# Ethernet.net
KiCad netlist of a schematic drawn in Altium Designer
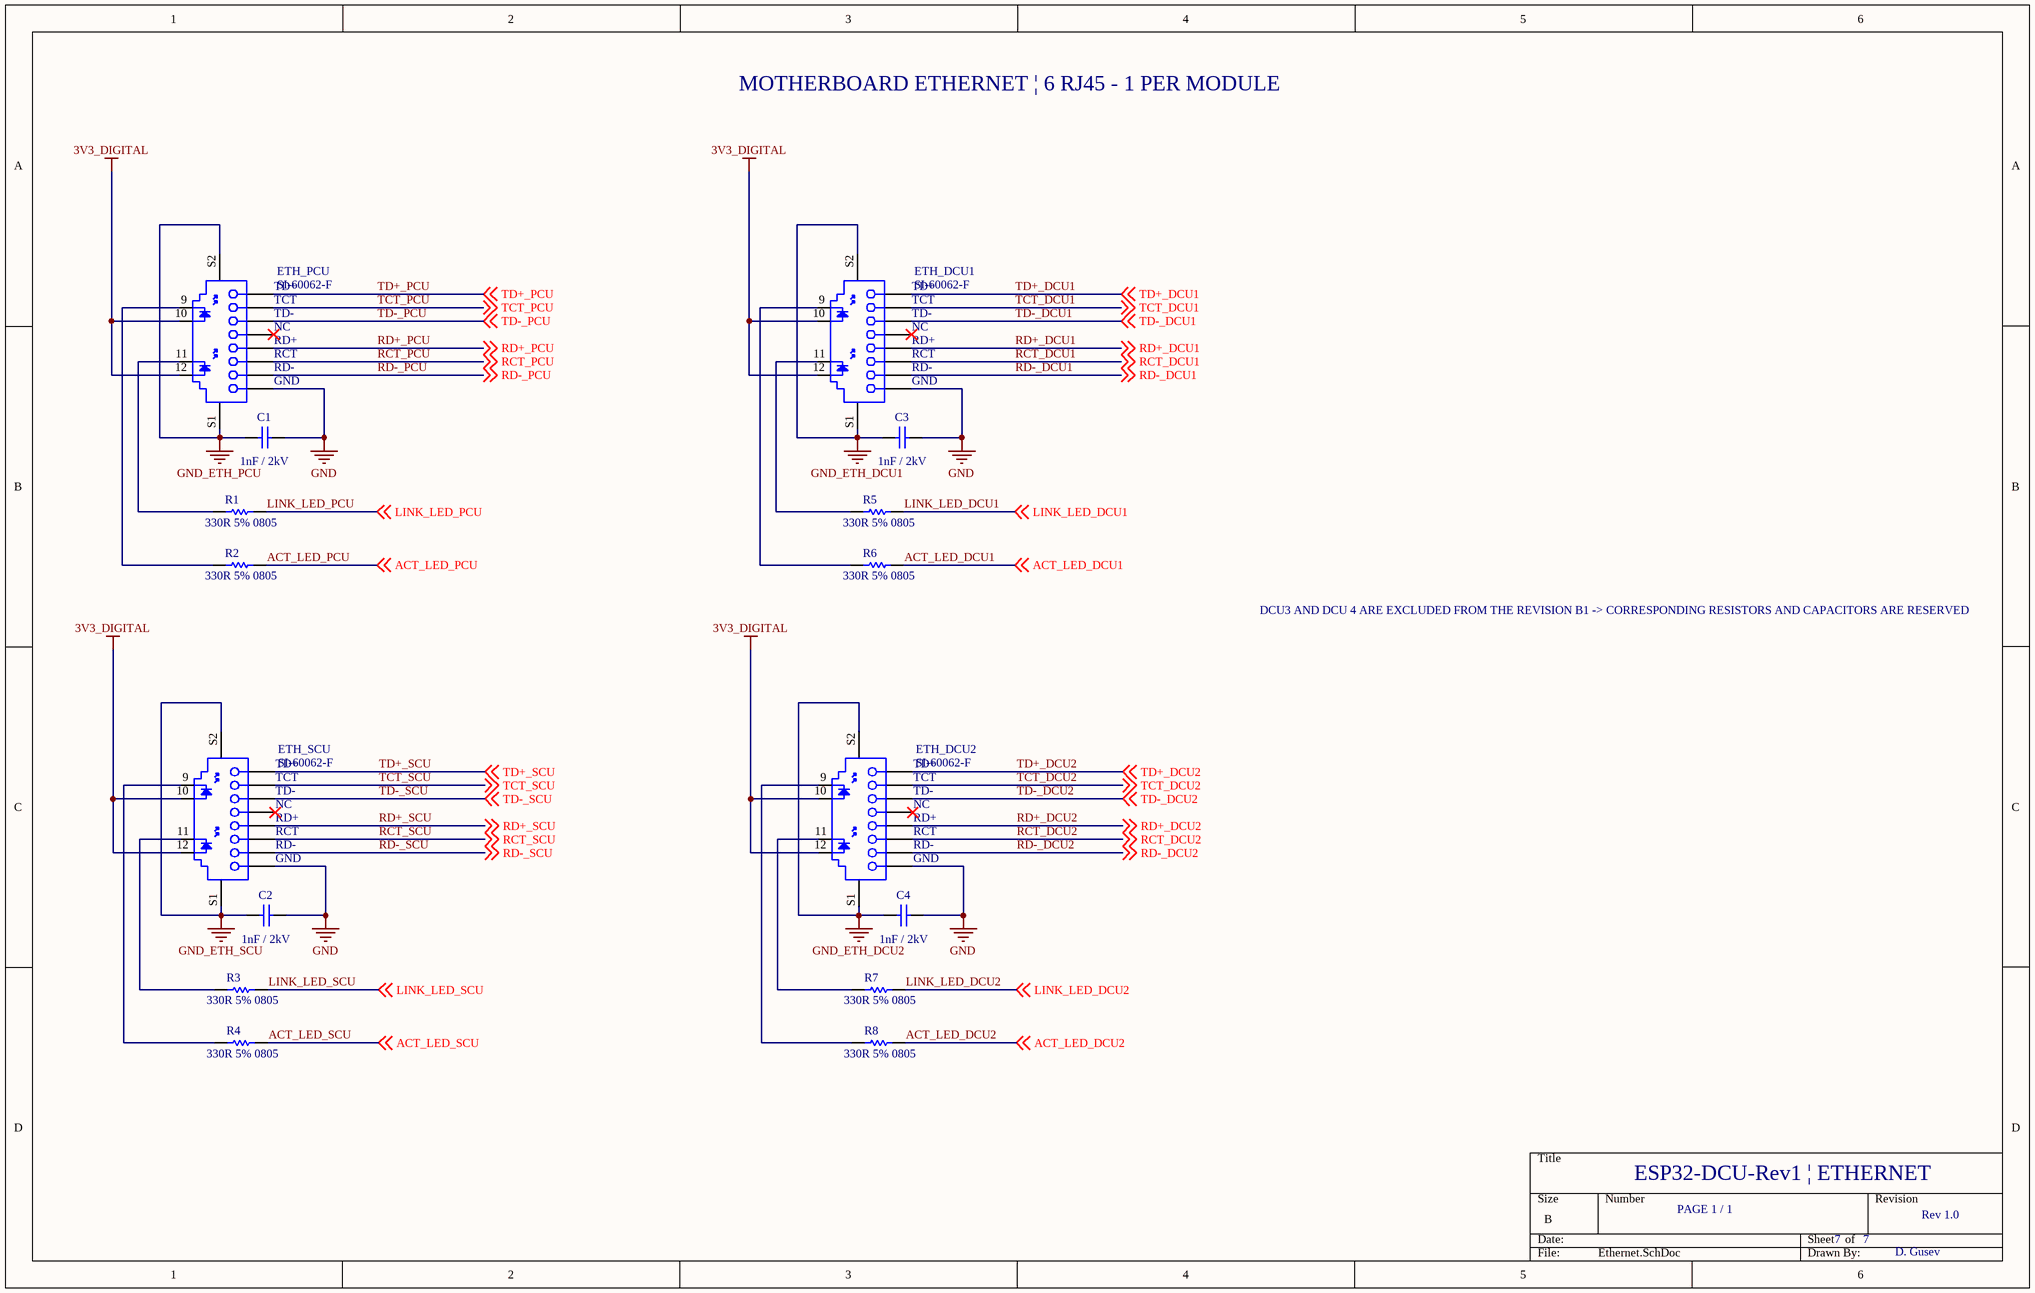
[diagram p0: Ethernet.SchDoc]

(export (version "E")
  (design (tool "Eeschema 10.0.6"))
  (components
    (comp (ref "C1")
      (value "1nF / 2kV")
      (footprint "CAPC4532X155X60LL30T35")
      (description "Chip Capacitor, 1000 pF, +/- 10%, 2000 V, -55 to 125 degC, 1812 (4532 Metric), RoHS, Tape and Reel")
      (fields (field (name "MANUFACTURER") "Kemet") (field (name "TOLERANCE") "±10%"))
      (libsource (lib "Altium Content Vault") (part "CAP-NP-2"))
    )
    (comp (ref "C2")
      (value "1nF / 2kV")
      (footprint "CAPC4532X155X60LL30T35")
      (description "Chip Capacitor, 1000 pF, +/- 10%, 2000 V, -55 to 125 degC, 1812 (4532 Metric), RoHS, Tape and Reel")
      (fields (field (name "MANUFACTURER") "Kemet") (field (name "TOLERANCE") "±10%"))
      (libsource (lib "Altium Content Vault") (part "CAP-NP-2"))
    )
    (comp (ref "C3")
      (value "1nF / 2kV")
      (footprint "CAPC4532X155X60LL30T35")
      (description "Chip Capacitor, 1000 pF, +/- 10%, 2000 V, -55 to 125 degC, 1812 (4532 Metric), RoHS, Tape and Reel")
      (fields (field (name "MANUFACTURER") "Kemet") (field (name "TOLERANCE") "±10%"))
      (libsource (lib "Altium Content Vault") (part "CAP-NP-2"))
    )
    (comp (ref "C4")
      (value "1nF / 2kV")
      (footprint "CAPC4532X155X60LL30T35")
      (description "Chip Capacitor, 1000 pF, +/- 10%, 2000 V, -55 to 125 degC, 1812 (4532 Metric), RoHS, Tape and Reel")
      (fields (field (name "MANUFACTURER") "Kemet") (field (name "TOLERANCE") "±10%"))
      (libsource (lib "Altium Content Vault") (part "CAP-NP-2"))
    )
    (comp (ref "ETH_DCU1")
      (value "SI-60062-F")
      (footprint "BELF-SI-60062-F_V")
      (description "1 Port RJ45 Magjack Connector with Yellow and Green LED, 10/100 Base-T, 12-Pin THD, RoHS, Tray")
      (fields (field (name "MANUFACTURER") "Bel Fuse"))
      (libsource (lib "Altium Content Vault") (part "RJ45-12-2SHLD"))
    )
    (comp (ref "ETH_DCU2")
      (value "SI-60062-F")
      (footprint "BELF-SI-60062-F_V")
      (description "1 Port RJ45 Magjack Connector with Yellow and Green LED, 10/100 Base-T, 12-Pin THD, RoHS, Tray")
      (fields (field (name "MANUFACTURER") "Bel Fuse"))
      (libsource (lib "Altium Content Vault") (part "RJ45-12-2SHLD"))
    )
    (comp (ref "ETH_PCU")
      (value "SI-60062-F")
      (footprint "BELF-SI-60062-F_V")
      (description "1 Port RJ45 Magjack Connector with Yellow and Green LED, 10/100 Base-T, 12-Pin THD, RoHS, Tray")
      (fields (field (name "MANUFACTURER") "Bel Fuse"))
      (libsource (lib "Altium Content Vault") (part "RJ45-12-2SHLD"))
    )
    (comp (ref "ETH_SCU")
      (value "SI-60062-F")
      (footprint "BELF-SI-60062-F_V")
      (description "1 Port RJ45 Magjack Connector with Yellow and Green LED, 10/100 Base-T, 12-Pin THD, RoHS, Tray")
      (fields (field (name "MANUFACTURER") "Bel Fuse"))
      (libsource (lib "Altium Content Vault") (part "RJ45-12-2SHLD"))
    )
    (comp (ref "R1")
      (value "330R 5% 0805")
      (footprint "RESC2013X60X35LL10T20")
      (description "Chip Resistor, 330 Ohm, +/- 1%, 125 mW, -55 to 155 degC, 0805 (2012 Metric), RoHS, Tape and Reel")
      (fields (field (name "MANUFACTURER") "Yageo") (field (name "TOLERANCE") "1%"))
      (libsource (lib "Altium Content Vault") (part "RES-2"))
    )
    (comp (ref "R2")
      (value "330R 5% 0805")
      (footprint "RESC2013X60X35LL10T20")
      (description "Chip Resistor, 330 Ohm, +/- 1%, 125 mW, -55 to 155 degC, 0805 (2012 Metric), RoHS, Tape and Reel")
      (fields (field (name "MANUFACTURER") "Yageo") (field (name "TOLERANCE") "1%"))
      (libsource (lib "Altium Content Vault") (part "RES-2"))
    )
    (comp (ref "R3")
      (value "330R 5% 0805")
      (footprint "RESC2013X60X35LL10T20")
      (description "Chip Resistor, 330 Ohm, +/- 1%, 125 mW, -55 to 155 degC, 0805 (2012 Metric), RoHS, Tape and Reel")
      (fields (field (name "MANUFACTURER") "Yageo") (field (name "TOLERANCE") "1%"))
      (libsource (lib "Altium Content Vault") (part "RES-2"))
    )
    (comp (ref "R4")
      (value "330R 5% 0805")
      (footprint "RESC2013X60X35LL10T20")
      (description "Chip Resistor, 330 Ohm, +/- 1%, 125 mW, -55 to 155 degC, 0805 (2012 Metric), RoHS, Tape and Reel")
      (fields (field (name "MANUFACTURER") "Yageo") (field (name "TOLERANCE") "1%"))
      (libsource (lib "Altium Content Vault") (part "RES-2"))
    )
    (comp (ref "R5")
      (value "330R 5% 0805")
      (footprint "RESC2013X60X35LL10T20")
      (description "Chip Resistor, 330 Ohm, +/- 1%, 125 mW, -55 to 155 degC, 0805 (2012 Metric), RoHS, Tape and Reel")
      (fields (field (name "MANUFACTURER") "Yageo") (field (name "TOLERANCE") "1%"))
      (libsource (lib "Altium Content Vault") (part "RES-2"))
    )
    (comp (ref "R6")
      (value "330R 5% 0805")
      (footprint "RESC2013X60X35LL10T20")
      (description "Chip Resistor, 330 Ohm, +/- 1%, 125 mW, -55 to 155 degC, 0805 (2012 Metric), RoHS, Tape and Reel")
      (fields (field (name "MANUFACTURER") "Yageo") (field (name "TOLERANCE") "1%"))
      (libsource (lib "Altium Content Vault") (part "RES-2"))
    )
    (comp (ref "R7")
      (value "330R 5% 0805")
      (footprint "RESC2013X60X35LL10T20")
      (description "Chip Resistor, 330 Ohm, +/- 1%, 125 mW, -55 to 155 degC, 0805 (2012 Metric), RoHS, Tape and Reel")
      (fields (field (name "MANUFACTURER") "Yageo") (field (name "TOLERANCE") "1%"))
      (libsource (lib "Altium Content Vault") (part "RES-2"))
    )
    (comp (ref "R8")
      (value "330R 5% 0805")
      (footprint "RESC2013X60X35LL10T20")
      (description "Chip Resistor, 330 Ohm, +/- 1%, 125 mW, -55 to 155 degC, 0805 (2012 Metric), RoHS, Tape and Reel")
      (fields (field (name "MANUFACTURER") "Yageo") (field (name "TOLERANCE") "1%"))
      (libsource (lib "Altium Content Vault") (part "RES-2"))
    )
  )
  (nets
    (net (code "1") (name "3V3_DIGITAL") (class "Default")
      (node (ref "ETH_DCU1") (pin "10") (pinfunction "10_10") (pintype "passive"))
      (node (ref "ETH_DCU1") (pin "12") (pinfunction "12_12") (pintype "passive"))
      (node (ref "ETH_DCU2") (pin "10") (pinfunction "10_10") (pintype "passive"))
      (node (ref "ETH_DCU2") (pin "12") (pinfunction "12_12") (pintype "passive"))
      (node (ref "ETH_PCU") (pin "10") (pinfunction "10_10") (pintype "passive"))
      (node (ref "ETH_PCU") (pin "12") (pinfunction "12_12") (pintype "passive"))
      (node (ref "ETH_SCU") (pin "10") (pinfunction "10_10") (pintype "passive"))
      (node (ref "ETH_SCU") (pin "12") (pinfunction "12_12") (pintype "passive"))
    )
    (net (code "2") (name "ACT_LED_DCU1") (class "Default")
      (node (ref "R6") (pin "2") (pinfunction "2_2") (pintype "passive"))
    )
    (net (code "3") (name "ACT_LED_DCU2") (class "Default")
      (node (ref "R8") (pin "2") (pinfunction "2_2") (pintype "passive"))
    )
    (net (code "4") (name "ACT_LED_PCU") (class "Default")
      (node (ref "R2") (pin "2") (pinfunction "2_2") (pintype "passive"))
    )
    (net (code "5") (name "ACT_LED_SCU") (class "Default")
      (node (ref "R4") (pin "2") (pinfunction "2_2") (pintype "passive"))
    )
    (net (code "6") (name "GND") (class "Default")
      (node (ref "C1") (pin "2") (pinfunction "2_2") (pintype "passive"))
      (node (ref "C2") (pin "2") (pinfunction "2_2") (pintype "passive"))
      (node (ref "C3") (pin "2") (pinfunction "2_2") (pintype "passive"))
      (node (ref "C4") (pin "2") (pinfunction "2_2") (pintype "passive"))
      (node (ref "ETH_DCU1") (pin "8") (pinfunction "GND_8") (pintype "passive"))
      (node (ref "ETH_DCU2") (pin "8") (pinfunction "GND_8") (pintype "passive"))
      (node (ref "ETH_PCU") (pin "8") (pinfunction "GND_8") (pintype "passive"))
      (node (ref "ETH_SCU") (pin "8") (pinfunction "GND_8") (pintype "passive"))
    )
    (net (code "7") (name "GND_ETH_DCU1") (class "Default")
      (node (ref "C3") (pin "1") (pinfunction "1_1") (pintype "passive"))
      (node (ref "ETH_DCU1") (pin "S1") (pinfunction "S1_S1") (pintype "passive"))
      (node (ref "ETH_DCU1") (pin "S2") (pinfunction "S2_S2") (pintype "passive"))
    )
    (net (code "8") (name "GND_ETH_DCU2") (class "Default")
      (node (ref "C4") (pin "1") (pinfunction "1_1") (pintype "passive"))
      (node (ref "ETH_DCU2") (pin "S1") (pinfunction "S1_S1") (pintype "passive"))
      (node (ref "ETH_DCU2") (pin "S2") (pinfunction "S2_S2") (pintype "passive"))
    )
    (net (code "9") (name "GND_ETH_PCU") (class "Default")
      (node (ref "C1") (pin "1") (pinfunction "1_1") (pintype "passive"))
      (node (ref "ETH_PCU") (pin "S1") (pinfunction "S1_S1") (pintype "passive"))
      (node (ref "ETH_PCU") (pin "S2") (pinfunction "S2_S2") (pintype "passive"))
    )
    (net (code "10") (name "GND_ETH_SCU") (class "Default")
      (node (ref "C2") (pin "1") (pinfunction "1_1") (pintype "passive"))
      (node (ref "ETH_SCU") (pin "S1") (pinfunction "S1_S1") (pintype "passive"))
      (node (ref "ETH_SCU") (pin "S2") (pinfunction "S2_S2") (pintype "passive"))
    )
    (net (code "11") (name "LINK_LED_DCU1") (class "Default")
      (node (ref "R5") (pin "2") (pinfunction "2_2") (pintype "passive"))
    )
    (net (code "12") (name "LINK_LED_DCU2") (class "Default")
      (node (ref "R7") (pin "2") (pinfunction "2_2") (pintype "passive"))
    )
    (net (code "13") (name "LINK_LED_PCU") (class "Default")
      (node (ref "R1") (pin "2") (pinfunction "2_2") (pintype "passive"))
    )
    (net (code "14") (name "LINK_LED_SCU") (class "Default")
      (node (ref "R3") (pin "2") (pinfunction "2_2") (pintype "passive"))
    )
    (net (code "15") (name "Net-(ETH_DCU1-Pad9)") (class "Default")
      (node (ref "ETH_DCU1") (pin "9") (pinfunction "9_9") (pintype "passive"))
      (node (ref "R6") (pin "1") (pinfunction "1_1") (pintype "passive"))
    )
    (net (code "16") (name "Net-(ETH_DCU1-Pad11)") (class "Default")
      (node (ref "ETH_DCU1") (pin "11") (pinfunction "11_11") (pintype "passive"))
      (node (ref "R5") (pin "1") (pinfunction "1_1") (pintype "passive"))
    )
    (net (code "17") (name "Net-(ETH_DCU2-Pad9)") (class "Default")
      (node (ref "ETH_DCU2") (pin "9") (pinfunction "9_9") (pintype "passive"))
      (node (ref "R8") (pin "1") (pinfunction "1_1") (pintype "passive"))
    )
    (net (code "18") (name "Net-(ETH_DCU2-Pad11)") (class "Default")
      (node (ref "ETH_DCU2") (pin "11") (pinfunction "11_11") (pintype "passive"))
      (node (ref "R7") (pin "1") (pinfunction "1_1") (pintype "passive"))
    )
    (net (code "19") (name "Net-(ETH_PCU-Pad9)") (class "Default")
      (node (ref "ETH_PCU") (pin "9") (pinfunction "9_9") (pintype "passive"))
      (node (ref "R2") (pin "1") (pinfunction "1_1") (pintype "passive"))
    )
    (net (code "20") (name "Net-(ETH_PCU-Pad11)") (class "Default")
      (node (ref "ETH_PCU") (pin "11") (pinfunction "11_11") (pintype "passive"))
      (node (ref "R1") (pin "1") (pinfunction "1_1") (pintype "passive"))
    )
    (net (code "21") (name "Net-(ETH_SCU-Pad9)") (class "Default")
      (node (ref "ETH_SCU") (pin "9") (pinfunction "9_9") (pintype "passive"))
      (node (ref "R4") (pin "1") (pinfunction "1_1") (pintype "passive"))
    )
    (net (code "22") (name "Net-(ETH_SCU-Pad11)") (class "Default")
      (node (ref "ETH_SCU") (pin "11") (pinfunction "11_11") (pintype "passive"))
      (node (ref "R3") (pin "1") (pinfunction "1_1") (pintype "passive"))
    )
    (net (code "23") (name "RCT_DCU1") (class "Default")
      (node (ref "ETH_DCU1") (pin "6") (pinfunction "RCT_6") (pintype "passive"))
    )
    (net (code "24") (name "RCT_DCU2") (class "Default")
      (node (ref "ETH_DCU2") (pin "6") (pinfunction "RCT_6") (pintype "passive"))
    )
    (net (code "25") (name "RCT_PCU") (class "Default")
      (node (ref "ETH_PCU") (pin "6") (pinfunction "RCT_6") (pintype "passive"))
    )
    (net (code "26") (name "RCT_SCU") (class "Default")
      (node (ref "ETH_SCU") (pin "6") (pinfunction "RCT_6") (pintype "passive"))
    )
    (net (code "27") (name "RD+_DCU1") (class "Default")
      (node (ref "ETH_DCU1") (pin "5") (pinfunction "RD+_5") (pintype "passive"))
    )
    (net (code "28") (name "RD+_DCU2") (class "Default")
      (node (ref "ETH_DCU2") (pin "5") (pinfunction "RD+_5") (pintype "passive"))
    )
    (net (code "29") (name "RD+_PCU") (class "Default")
      (node (ref "ETH_PCU") (pin "5") (pinfunction "RD+_5") (pintype "passive"))
    )
    (net (code "30") (name "RD+_SCU") (class "Default")
      (node (ref "ETH_SCU") (pin "5") (pinfunction "RD+_5") (pintype "passive"))
    )
    (net (code "31") (name "RD-_DCU1") (class "Default")
      (node (ref "ETH_DCU1") (pin "7") (pinfunction "RD-_7") (pintype "passive"))
    )
    (net (code "32") (name "RD-_DCU2") (class "Default")
      (node (ref "ETH_DCU2") (pin "7") (pinfunction "RD-_7") (pintype "passive"))
    )
    (net (code "33") (name "RD-_PCU") (class "Default")
      (node (ref "ETH_PCU") (pin "7") (pinfunction "RD-_7") (pintype "passive"))
    )
    (net (code "34") (name "RD-_SCU") (class "Default")
      (node (ref "ETH_SCU") (pin "7") (pinfunction "RD-_7") (pintype "passive"))
    )
    (net (code "35") (name "TCT_DCU1") (class "Default")
      (node (ref "ETH_DCU1") (pin "2") (pinfunction "TCT_2") (pintype "passive"))
    )
    (net (code "36") (name "TCT_DCU2") (class "Default")
      (node (ref "ETH_DCU2") (pin "2") (pinfunction "TCT_2") (pintype "passive"))
    )
    (net (code "37") (name "TCT_PCU") (class "Default")
      (node (ref "ETH_PCU") (pin "2") (pinfunction "TCT_2") (pintype "passive"))
    )
    (net (code "38") (name "TCT_SCU") (class "Default")
      (node (ref "ETH_SCU") (pin "2") (pinfunction "TCT_2") (pintype "passive"))
    )
    (net (code "39") (name "TD+_DCU1") (class "Default")
      (node (ref "ETH_DCU1") (pin "1") (pinfunction "TD+_1") (pintype "passive"))
    )
    (net (code "40") (name "TD+_DCU2") (class "Default")
      (node (ref "ETH_DCU2") (pin "1") (pinfunction "TD+_1") (pintype "passive"))
    )
    (net (code "41") (name "TD+_PCU") (class "Default")
      (node (ref "ETH_PCU") (pin "1") (pinfunction "TD+_1") (pintype "passive"))
    )
    (net (code "42") (name "TD+_SCU") (class "Default")
      (node (ref "ETH_SCU") (pin "1") (pinfunction "TD+_1") (pintype "passive"))
    )
    (net (code "43") (name "TD-_DCU1") (class "Default")
      (node (ref "ETH_DCU1") (pin "3") (pinfunction "TD-_3") (pintype "passive"))
    )
    (net (code "44") (name "TD-_DCU2") (class "Default")
      (node (ref "ETH_DCU2") (pin "3") (pinfunction "TD-_3") (pintype "passive"))
    )
    (net (code "45") (name "TD-_PCU") (class "Default")
      (node (ref "ETH_PCU") (pin "3") (pinfunction "TD-_3") (pintype "passive"))
    )
    (net (code "46") (name "TD-_SCU") (class "Default")
      (node (ref "ETH_SCU") (pin "3") (pinfunction "TD-_3") (pintype "passive"))
    )
    (net (code "47") (name "unconnected-(ETH_DCU1-NC-Pad4)") (class "Default")
      (node (ref "ETH_DCU1") (pin "4") (pinfunction "NC_4") (pintype "passive+no_connect"))
    )
    (net (code "48") (name "unconnected-(ETH_DCU2-NC-Pad4)") (class "Default")
      (node (ref "ETH_DCU2") (pin "4") (pinfunction "NC_4") (pintype "passive+no_connect"))
    )
    (net (code "49") (name "unconnected-(ETH_PCU-NC-Pad4)") (class "Default")
      (node (ref "ETH_PCU") (pin "4") (pinfunction "NC_4") (pintype "passive+no_connect"))
    )
    (net (code "50") (name "unconnected-(ETH_SCU-NC-Pad4)") (class "Default")
      (node (ref "ETH_SCU") (pin "4") (pinfunction "NC_4") (pintype "passive+no_connect"))
    )
  )
)
